# Seguidor.net
KiCad netlist of a schematic drawn in EAGLE
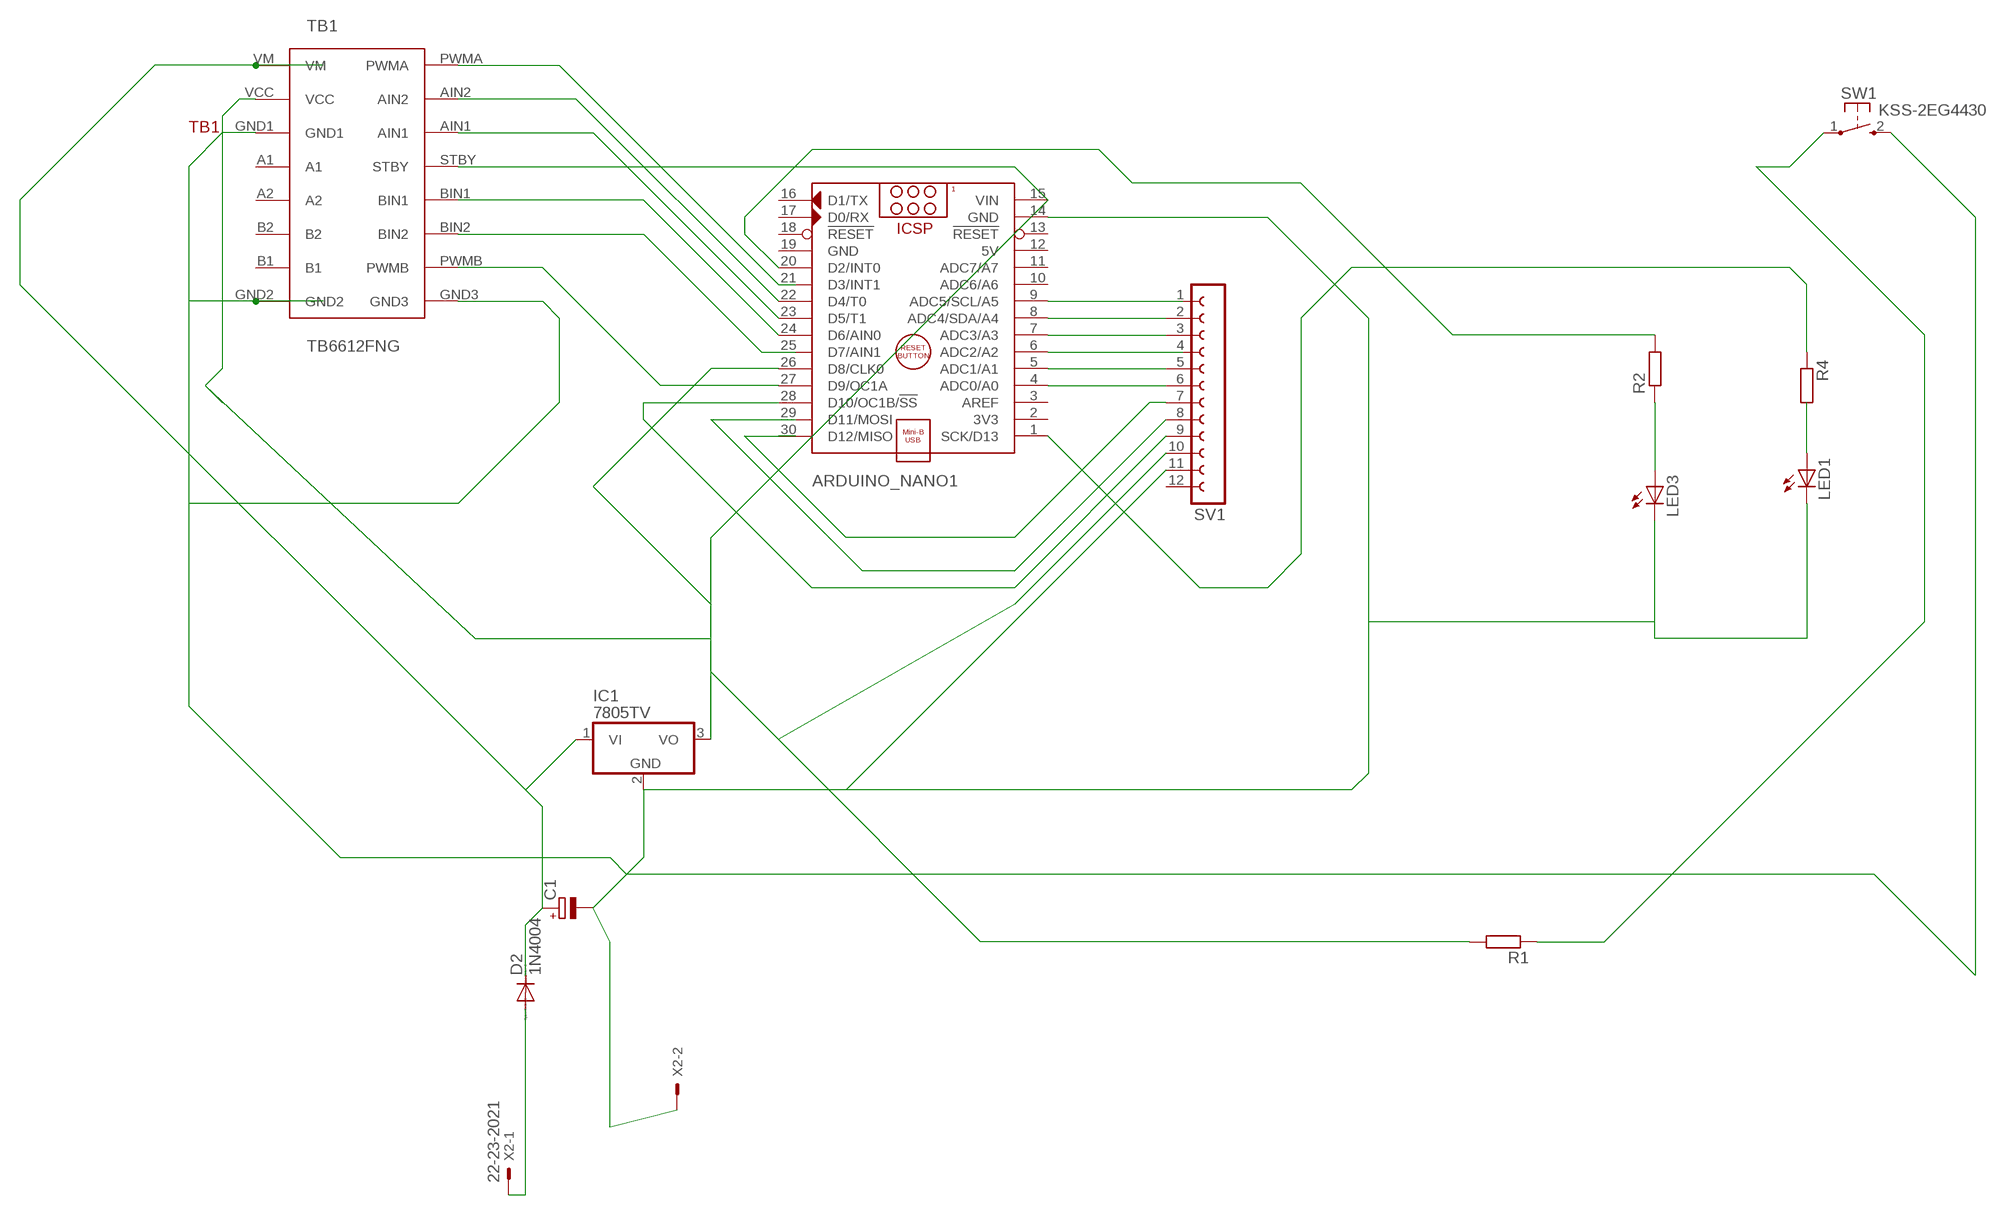
[diagram p0: schematic, sheet 1]

(export (version "E")
  (design (tool "Eeschema 10.0.6"))
  (components
    (comp (ref "ARDUINO_NANO1")
      (value "ARDUINO_NANO")
      (footprint "eagle-import:ARDUINO_NANO")
      (libsource (lib "eagle-import") (part "ARDUINO_NANO"))
    )
    (comp (ref "C1")
      (value "CPOL-EUE3.5-8")
      (footprint "eagle-import:E3,5-8")
      (libsource (lib "eagle-import") (part "CPOL-EUE3.5-8"))
    )
    (comp (ref "D2")
      (value "1N4004")
      (footprint "eagle-import:DO41-10")
      (libsource (lib "eagle-import") (part "1N4004"))
    )
    (comp (ref "IC1")
      (value "7805TV")
      (footprint "eagle-import:TO220V")
      (libsource (lib "eagle-import") (part "78TV05"))
    )
    (comp (ref "LED1")
      (value "LED5MM")
      (footprint "eagle-import:LED5MM")
      (libsource (lib "eagle-import") (part "LED5MM"))
    )
    (comp (ref "LED3")
      (value "LED5MM")
      (footprint "eagle-import:LED5MM")
      (libsource (lib "eagle-import") (part "LED5MM"))
    )
    (comp (ref "R1")
      (value "R-EU_0207/12")
      (footprint "eagle-import:0207_12")
      (libsource (lib "eagle-import") (part "R-EU_0207/12"))
    )
    (comp (ref "R2")
      (value "R-EU_0207/12")
      (footprint "eagle-import:0207_12")
      (libsource (lib "eagle-import") (part "R-EU_0207/12"))
    )
    (comp (ref "R4")
      (value "R-EU_0207/12")
      (footprint "eagle-import:0207_12")
      (libsource (lib "eagle-import") (part "R-EU_0207/12"))
    )
    (comp (ref "SV1")
      (value "FE12-1")
      (footprint "eagle-import:FE12")
      (libsource (lib "eagle-import") (part "FE12-1"))
    )
    (comp (ref "SW1")
      (value "KSS-2EG4430")
      (footprint "eagle-import:KSS-2EG4430")
      (libsource (lib "eagle-import") (part "KSS-2EG4430"))
    )
    (comp (ref "TB1")
      (value "TB6612FNG")
      (footprint "eagle-import:TB6612FNG")
      (libsource (lib "eagle-import") (part "TB6612FNG"))
    )
    (comp (ref "X2")
      (value "22-23-2021")
      (footprint "eagle-import:22-23-2021")
      (fields (field (name "MF") "MOLEX"))
      (libsource (lib "eagle-import") (part "22-23-2021"))
    )
  )
  (nets
    (net (code "1") (name "/5V") (class "Default")
      (node (ref "ARDUINO_NANO1") (pin "12") (pinfunction "5V_12") (pintype "power_in"))
    )
    (net (code "2") (name "/GND") (class "Default")
      (node (ref "ARDUINO_NANO1") (pin "19") (pinfunction "GND_19") (pintype "power_in"))
    )
    (net (code "3") (name "Net-(ARDUINO_NANO1-ADC0{slash}A0)") (class "Default")
      (node (ref "ARDUINO_NANO1") (pin "4") (pinfunction "ADC0/A0_4") (pintype "bidirectional"))
      (node (ref "SV1") (pin "6") (pinfunction "6_6") (pintype "passive"))
    )
    (net (code "4") (name "Net-(ARDUINO_NANO1-ADC1{slash}A1)") (class "Default")
      (node (ref "ARDUINO_NANO1") (pin "5") (pinfunction "ADC1/A1_5") (pintype "bidirectional"))
      (node (ref "SV1") (pin "5") (pinfunction "5_5") (pintype "passive"))
    )
    (net (code "5") (name "Net-(ARDUINO_NANO1-ADC2{slash}A2)") (class "Default")
      (node (ref "ARDUINO_NANO1") (pin "6") (pinfunction "ADC2/A2_6") (pintype "bidirectional"))
      (node (ref "SV1") (pin "4") (pinfunction "4_4") (pintype "passive"))
    )
    (net (code "6") (name "Net-(ARDUINO_NANO1-ADC3{slash}A3)") (class "Default")
      (node (ref "ARDUINO_NANO1") (pin "7") (pinfunction "ADC3/A3_7") (pintype "bidirectional"))
      (node (ref "SV1") (pin "3") (pinfunction "3_3") (pintype "passive"))
    )
    (net (code "7") (name "Net-(ARDUINO_NANO1-ADC4{slash}SDA{slash}A4)") (class "Default")
      (node (ref "ARDUINO_NANO1") (pin "8") (pinfunction "ADC4/SDA/A4_8") (pintype "bidirectional"))
      (node (ref "SV1") (pin "2") (pinfunction "2_2") (pintype "passive"))
    )
    (net (code "8") (name "Net-(ARDUINO_NANO1-ADC5{slash}SCL{slash}A5)") (class "Default")
      (node (ref "ARDUINO_NANO1") (pin "9") (pinfunction "ADC5/SCL/A5_9") (pintype "bidirectional"))
      (node (ref "SV1") (pin "1") (pinfunction "1_1") (pintype "passive"))
    )
    (net (code "9") (name "Net-(ARDUINO_NANO1-D2{slash}INT0)") (class "Default")
      (node (ref "ARDUINO_NANO1") (pin "20") (pinfunction "D2/INT0_20") (pintype "bidirectional"))
      (node (ref "R2") (pin "2") (pinfunction "2_2") (pintype "passive"))
    )
    (net (code "10") (name "Net-(ARDUINO_NANO1-D3{slash}INT1)") (class "Default")
      (node (ref "ARDUINO_NANO1") (pin "21") (pinfunction "D3/INT1_21") (pintype "bidirectional"))
      (node (ref "TB1") (pin "PWMA") (pinfunction "PWMA_PWMA") (pintype "bidirectional"))
    )
    (net (code "11") (name "Net-(ARDUINO_NANO1-D4{slash}T0)") (class "Default")
      (node (ref "ARDUINO_NANO1") (pin "22") (pinfunction "D4/T0_22") (pintype "bidirectional"))
      (node (ref "TB1") (pin "AIN2") (pinfunction "AIN2_AIN2") (pintype "bidirectional"))
    )
    (net (code "12") (name "Net-(ARDUINO_NANO1-D5{slash}T1)") (class "Default")
      (node (ref "ARDUINO_NANO1") (pin "23") (pinfunction "D5/T1_23") (pintype "bidirectional"))
      (node (ref "TB1") (pin "AIN1") (pinfunction "AIN1_AIN1") (pintype "bidirectional"))
    )
    (net (code "13") (name "Net-(ARDUINO_NANO1-D6{slash}AIN0)") (class "Default")
      (node (ref "ARDUINO_NANO1") (pin "24") (pinfunction "D6/AIN0_24") (pintype "bidirectional"))
      (node (ref "TB1") (pin "BIN1") (pinfunction "BIN1_BIN1") (pintype "bidirectional"))
    )
    (net (code "14") (name "Net-(ARDUINO_NANO1-D7{slash}AIN1)") (class "Default")
      (node (ref "ARDUINO_NANO1") (pin "25") (pinfunction "D7/AIN1_25") (pintype "bidirectional"))
      (node (ref "TB1") (pin "BIN2") (pinfunction "BIN2_BIN2") (pintype "bidirectional"))
    )
    (net (code "15") (name "Net-(ARDUINO_NANO1-D8{slash}CLK0)") (class "Default")
      (node (ref "ARDUINO_NANO1") (pin "15") (pinfunction "VIN_15") (pintype "power_in"))
      (node (ref "ARDUINO_NANO1") (pin "26") (pinfunction "D8/CLK0_26") (pintype "bidirectional"))
      (node (ref "IC1") (pin "3") (pinfunction "VO_3") (pintype "passive"))
      (node (ref "R1") (pin "2") (pinfunction "2_2") (pintype "passive"))
      (node (ref "SV1") (pin "10") (pinfunction "10_10") (pintype "passive"))
      (node (ref "TB1") (pin "STBY") (pinfunction "STBY_STBY") (pintype "bidirectional"))
      (node (ref "TB1") (pin "VCC") (pinfunction "VCC_VCC") (pintype "bidirectional"))
    )
    (net (code "16") (name "Net-(ARDUINO_NANO1-D9{slash}OC1A)") (class "Default")
      (node (ref "ARDUINO_NANO1") (pin "27") (pinfunction "D9/OC1A_27") (pintype "bidirectional"))
      (node (ref "TB1") (pin "PWMB") (pinfunction "PWMB_PWMB") (pintype "bidirectional"))
    )
    (net (code "17") (name "Net-(ARDUINO_NANO1-D10{slash}OC1B{slash}~{SS})") (class "Default")
      (node (ref "ARDUINO_NANO1") (pin "28") (pinfunction "D10/OC1B/~{SS}_28") (pintype "bidirectional"))
      (node (ref "SV1") (pin "9") (pinfunction "9_9") (pintype "passive"))
    )
    (net (code "18") (name "Net-(ARDUINO_NANO1-D11{slash}MOSI)") (class "Default")
      (node (ref "ARDUINO_NANO1") (pin "29") (pinfunction "D11/MOSI_29") (pintype "bidirectional"))
      (node (ref "SV1") (pin "8") (pinfunction "8_8") (pintype "passive"))
    )
    (net (code "19") (name "Net-(ARDUINO_NANO1-D12{slash}MISO)") (class "Default")
      (node (ref "ARDUINO_NANO1") (pin "30") (pinfunction "D12/MISO_30") (pintype "bidirectional"))
      (node (ref "SV1") (pin "7") (pinfunction "7_7") (pintype "passive"))
    )
    (net (code "20") (name "Net-(ARDUINO_NANO1-SCK{slash}D13)") (class "Default")
      (node (ref "ARDUINO_NANO1") (pin "1") (pinfunction "SCK/D13_1") (pintype "bidirectional"))
      (node (ref "R4") (pin "1") (pinfunction "1_1") (pintype "passive"))
    )
    (net (code "21") (name "Net-(IC1-GND)") (class "Default")
      (node (ref "ARDUINO_NANO1") (pin "14") (pinfunction "GND_14") (pintype "power_in"))
      (node (ref "C1") (pin "-") (pinfunction "-_-") (pintype "passive"))
      (node (ref "IC1") (pin "2") (pinfunction "GND_2") (pintype "passive"))
      (node (ref "LED1") (pin "K") (pinfunction "C_K") (pintype "passive"))
      (node (ref "LED3") (pin "K") (pinfunction "C_K") (pintype "passive"))
      (node (ref "SV1") (pin "11") (pinfunction "11_11") (pintype "passive"))
      (node (ref "SW1") (pin "2") (pinfunction "S_2") (pintype "passive"))
      (node (ref "TB1") (pin "GND1") (pinfunction "GND1_GND1") (pintype "bidirectional"))
      (node (ref "TB1") (pin "GND2") (pinfunction "GND2_GND2") (pintype "bidirectional"))
      (node (ref "TB1") (pin "GND3") (pinfunction "GND3_GND3") (pintype "bidirectional"))
      (node (ref "X2") (pin "2") (pinfunction "S_2") (pintype "passive"))
    )
    (net (code "22") (name "Net-(IC1-VI)") (class "Default")
      (node (ref "C1") (pin "+") (pinfunction "+_+") (pintype "passive"))
      (node (ref "D2") (pin "C") (pinfunction "C_C") (pintype "passive"))
      (node (ref "IC1") (pin "1") (pinfunction "VI_1") (pintype "input"))
      (node (ref "TB1") (pin "VM") (pinfunction "VM_VM") (pintype "bidirectional"))
    )
    (net (code "23") (name "Net-(LED1-PadA)") (class "Default")
      (node (ref "LED1") (pin "A") (pinfunction "A_A") (pintype "passive"))
      (node (ref "R4") (pin "2") (pinfunction "2_2") (pintype "passive"))
    )
    (net (code "24") (name "Net-(LED3-PadA)") (class "Default")
      (node (ref "LED3") (pin "A") (pinfunction "A_A") (pintype "passive"))
      (node (ref "R2") (pin "1") (pinfunction "1_1") (pintype "passive"))
    )
    (net (code "25") (name "Net-(SW1-P)") (class "Default")
      (node (ref "R1") (pin "1") (pinfunction "1_1") (pintype "passive"))
      (node (ref "SW1") (pin "1") (pinfunction "P_1") (pintype "passive"))
    )
    (net (code "26") (name "Net-(X2A-S)") (class "Default")
      (node (ref "D2") (pin "A") (pinfunction "A_A") (pintype "passive"))
      (node (ref "X2") (pin "1") (pinfunction "S_1") (pintype "passive"))
    )
    (net (code "27") (name "unconnected-(ARDUINO_NANO1-3V3-Pad2)") (class "Default")
      (node (ref "ARDUINO_NANO1") (pin "2") (pinfunction "3V3_2") (pintype "output"))
    )
    (net (code "28") (name "unconnected-(ARDUINO_NANO1-ADC6{slash}A6-Pad10)") (class "Default")
      (node (ref "ARDUINO_NANO1") (pin "10") (pinfunction "ADC6/A6_10") (pintype "bidirectional"))
    )
    (net (code "29") (name "unconnected-(ARDUINO_NANO1-ADC7{slash}A7-Pad11)") (class "Default")
      (node (ref "ARDUINO_NANO1") (pin "11") (pinfunction "ADC7/A7_11") (pintype "bidirectional"))
    )
    (net (code "30") (name "unconnected-(ARDUINO_NANO1-AREF-Pad3)") (class "Default")
      (node (ref "ARDUINO_NANO1") (pin "3") (pinfunction "AREF_3") (pintype "input"))
    )
    (net (code "31") (name "unconnected-(ARDUINO_NANO1-D0{slash}RX-Pad17)") (class "Default")
      (node (ref "ARDUINO_NANO1") (pin "17") (pinfunction "D0/RX_17") (pintype "bidirectional"))
    )
    (net (code "32") (name "unconnected-(ARDUINO_NANO1-D1{slash}TX-Pad16)") (class "Default")
      (node (ref "ARDUINO_NANO1") (pin "16") (pinfunction "D1/TX_16") (pintype "bidirectional"))
    )
    (net (code "33") (name "unconnected-(ARDUINO_NANO1-~{RESET}-Pad13)") (class "Default")
      (node (ref "ARDUINO_NANO1") (pin "13") (pinfunction "~{RESET}_13") (pintype "input"))
    )
    (net (code "34") (name "unconnected-(ARDUINO_NANO1-~{RESET}-Pad18)") (class "Default")
      (node (ref "ARDUINO_NANO1") (pin "18") (pinfunction "~{RESET}_18") (pintype "input"))
    )
    (net (code "35") (name "unconnected-(SV1-Pad12)") (class "Default")
      (node (ref "SV1") (pin "12") (pinfunction "12_12") (pintype "passive"))
    )
    (net (code "36") (name "unconnected-(TB1-PadA1)") (class "Default")
      (node (ref "TB1") (pin "A1") (pinfunction "A1_A1") (pintype "bidirectional"))
    )
    (net (code "37") (name "unconnected-(TB1-PadA2)") (class "Default")
      (node (ref "TB1") (pin "A2") (pinfunction "A2_A2") (pintype "bidirectional"))
    )
    (net (code "38") (name "unconnected-(TB1-PadB1)") (class "Default")
      (node (ref "TB1") (pin "B1") (pinfunction "B1_B1") (pintype "bidirectional"))
    )
    (net (code "39") (name "unconnected-(TB1-PadB2)") (class "Default")
      (node (ref "TB1") (pin "B2") (pinfunction "B2_B2") (pintype "bidirectional"))
    )
  )
)
